# stereo-jack.net
KiCad netlist of a schematic drawn in EAGLE
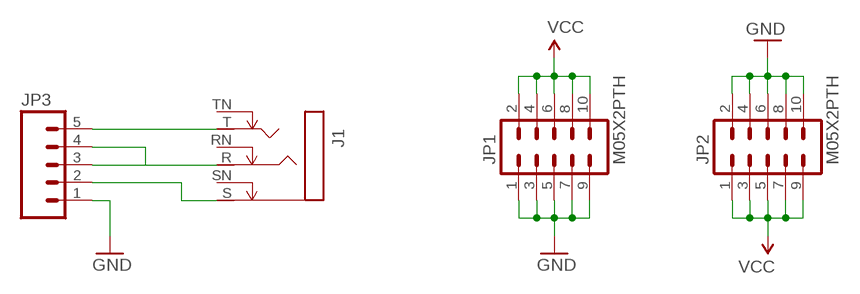
[diagram p0: schematic, sheet 1]

(export (version "E")
  (design (tool "Eeschema 10.0.6"))
  (components
    (comp (ref "J1")
      (value "STEREOSW")
      (footprint "eagle-import:NMJ6HCD2")
      (libsource (lib "eagle-import") (part "STEREOSW"))
    )
    (comp (ref "JP1")
      (value "M05X2PTH")
      (footprint "eagle-import:AVR_ICSP")
      (libsource (lib "eagle-import") (part "M05X2PTH"))
    )
    (comp (ref "JP2")
      (value "M05X2PTH")
      (footprint "eagle-import:AVR_ICSP")
      (libsource (lib "eagle-import") (part "M05X2PTH"))
    )
    (comp (ref "JP3")
      (value "M05PTH")
      (footprint "eagle-import:1X05")
      (libsource (lib "eagle-import") (part "M05PTH"))
    )
  )
  (nets
    (net (code "1") (name "GND") (class "Default")
      (node (ref "JP1") (pin "1") (pinfunction "1_1") (pintype "passive"))
      (node (ref "JP1") (pin "3") (pinfunction "3_3") (pintype "passive"))
      (node (ref "JP1") (pin "5") (pinfunction "5_5") (pintype "passive"))
      (node (ref "JP1") (pin "7") (pinfunction "7_7") (pintype "passive"))
      (node (ref "JP1") (pin "9") (pinfunction "9_9") (pintype "passive"))
      (node (ref "JP2") (pin "10") (pinfunction "10_10") (pintype "passive"))
      (node (ref "JP2") (pin "2") (pinfunction "2_2") (pintype "passive"))
      (node (ref "JP2") (pin "4") (pinfunction "4_4") (pintype "passive"))
      (node (ref "JP2") (pin "6") (pinfunction "6_6") (pintype "passive"))
      (node (ref "JP2") (pin "8") (pinfunction "8_8") (pintype "passive"))
      (node (ref "JP3") (pin "1") (pinfunction "1_1") (pintype "passive"))
    )
    (net (code "2") (name "Net-(J1-PadR)") (class "Default")
      (node (ref "J1") (pin "R") (pinfunction "R_R") (pintype "passive"))
      (node (ref "JP3") (pin "3") (pinfunction "3_3") (pintype "passive"))
      (node (ref "JP3") (pin "4") (pinfunction "4_4") (pintype "passive"))
    )
    (net (code "3") (name "Net-(J1-PadS)") (class "Default")
      (node (ref "J1") (pin "S") (pinfunction "S_S") (pintype "passive"))
      (node (ref "JP3") (pin "2") (pinfunction "2_2") (pintype "passive"))
    )
    (net (code "4") (name "Net-(J1-PadT)") (class "Default")
      (node (ref "J1") (pin "T") (pinfunction "T_T") (pintype "passive"))
      (node (ref "JP3") (pin "5") (pinfunction "5_5") (pintype "passive"))
    )
    (net (code "5") (name "VCC") (class "Default")
      (node (ref "JP1") (pin "10") (pinfunction "10_10") (pintype "passive"))
      (node (ref "JP1") (pin "2") (pinfunction "2_2") (pintype "passive"))
      (node (ref "JP1") (pin "4") (pinfunction "4_4") (pintype "passive"))
      (node (ref "JP1") (pin "6") (pinfunction "6_6") (pintype "passive"))
      (node (ref "JP1") (pin "8") (pinfunction "8_8") (pintype "passive"))
      (node (ref "JP2") (pin "1") (pinfunction "1_1") (pintype "passive"))
      (node (ref "JP2") (pin "3") (pinfunction "3_3") (pintype "passive"))
      (node (ref "JP2") (pin "5") (pinfunction "5_5") (pintype "passive"))
      (node (ref "JP2") (pin "7") (pinfunction "7_7") (pintype "passive"))
      (node (ref "JP2") (pin "9") (pinfunction "9_9") (pintype "passive"))
    )
    (net (code "6") (name "unconnected-(J1-PadRN)") (class "Default")
      (node (ref "J1") (pin "RN") (pinfunction "RN_RN") (pintype "passive"))
    )
    (net (code "7") (name "unconnected-(J1-PadSN)") (class "Default")
      (node (ref "J1") (pin "SN") (pinfunction "SN_SN") (pintype "passive"))
    )
    (net (code "8") (name "unconnected-(J1-PadTN)") (class "Default")
      (node (ref "J1") (pin "TN") (pinfunction "TN_TN") (pintype "passive"))
    )
  )
)
